# 1-Schematic_EMWAVER_UNO_V3.net
KiCad netlist of a schematic drawn in EasyEDA
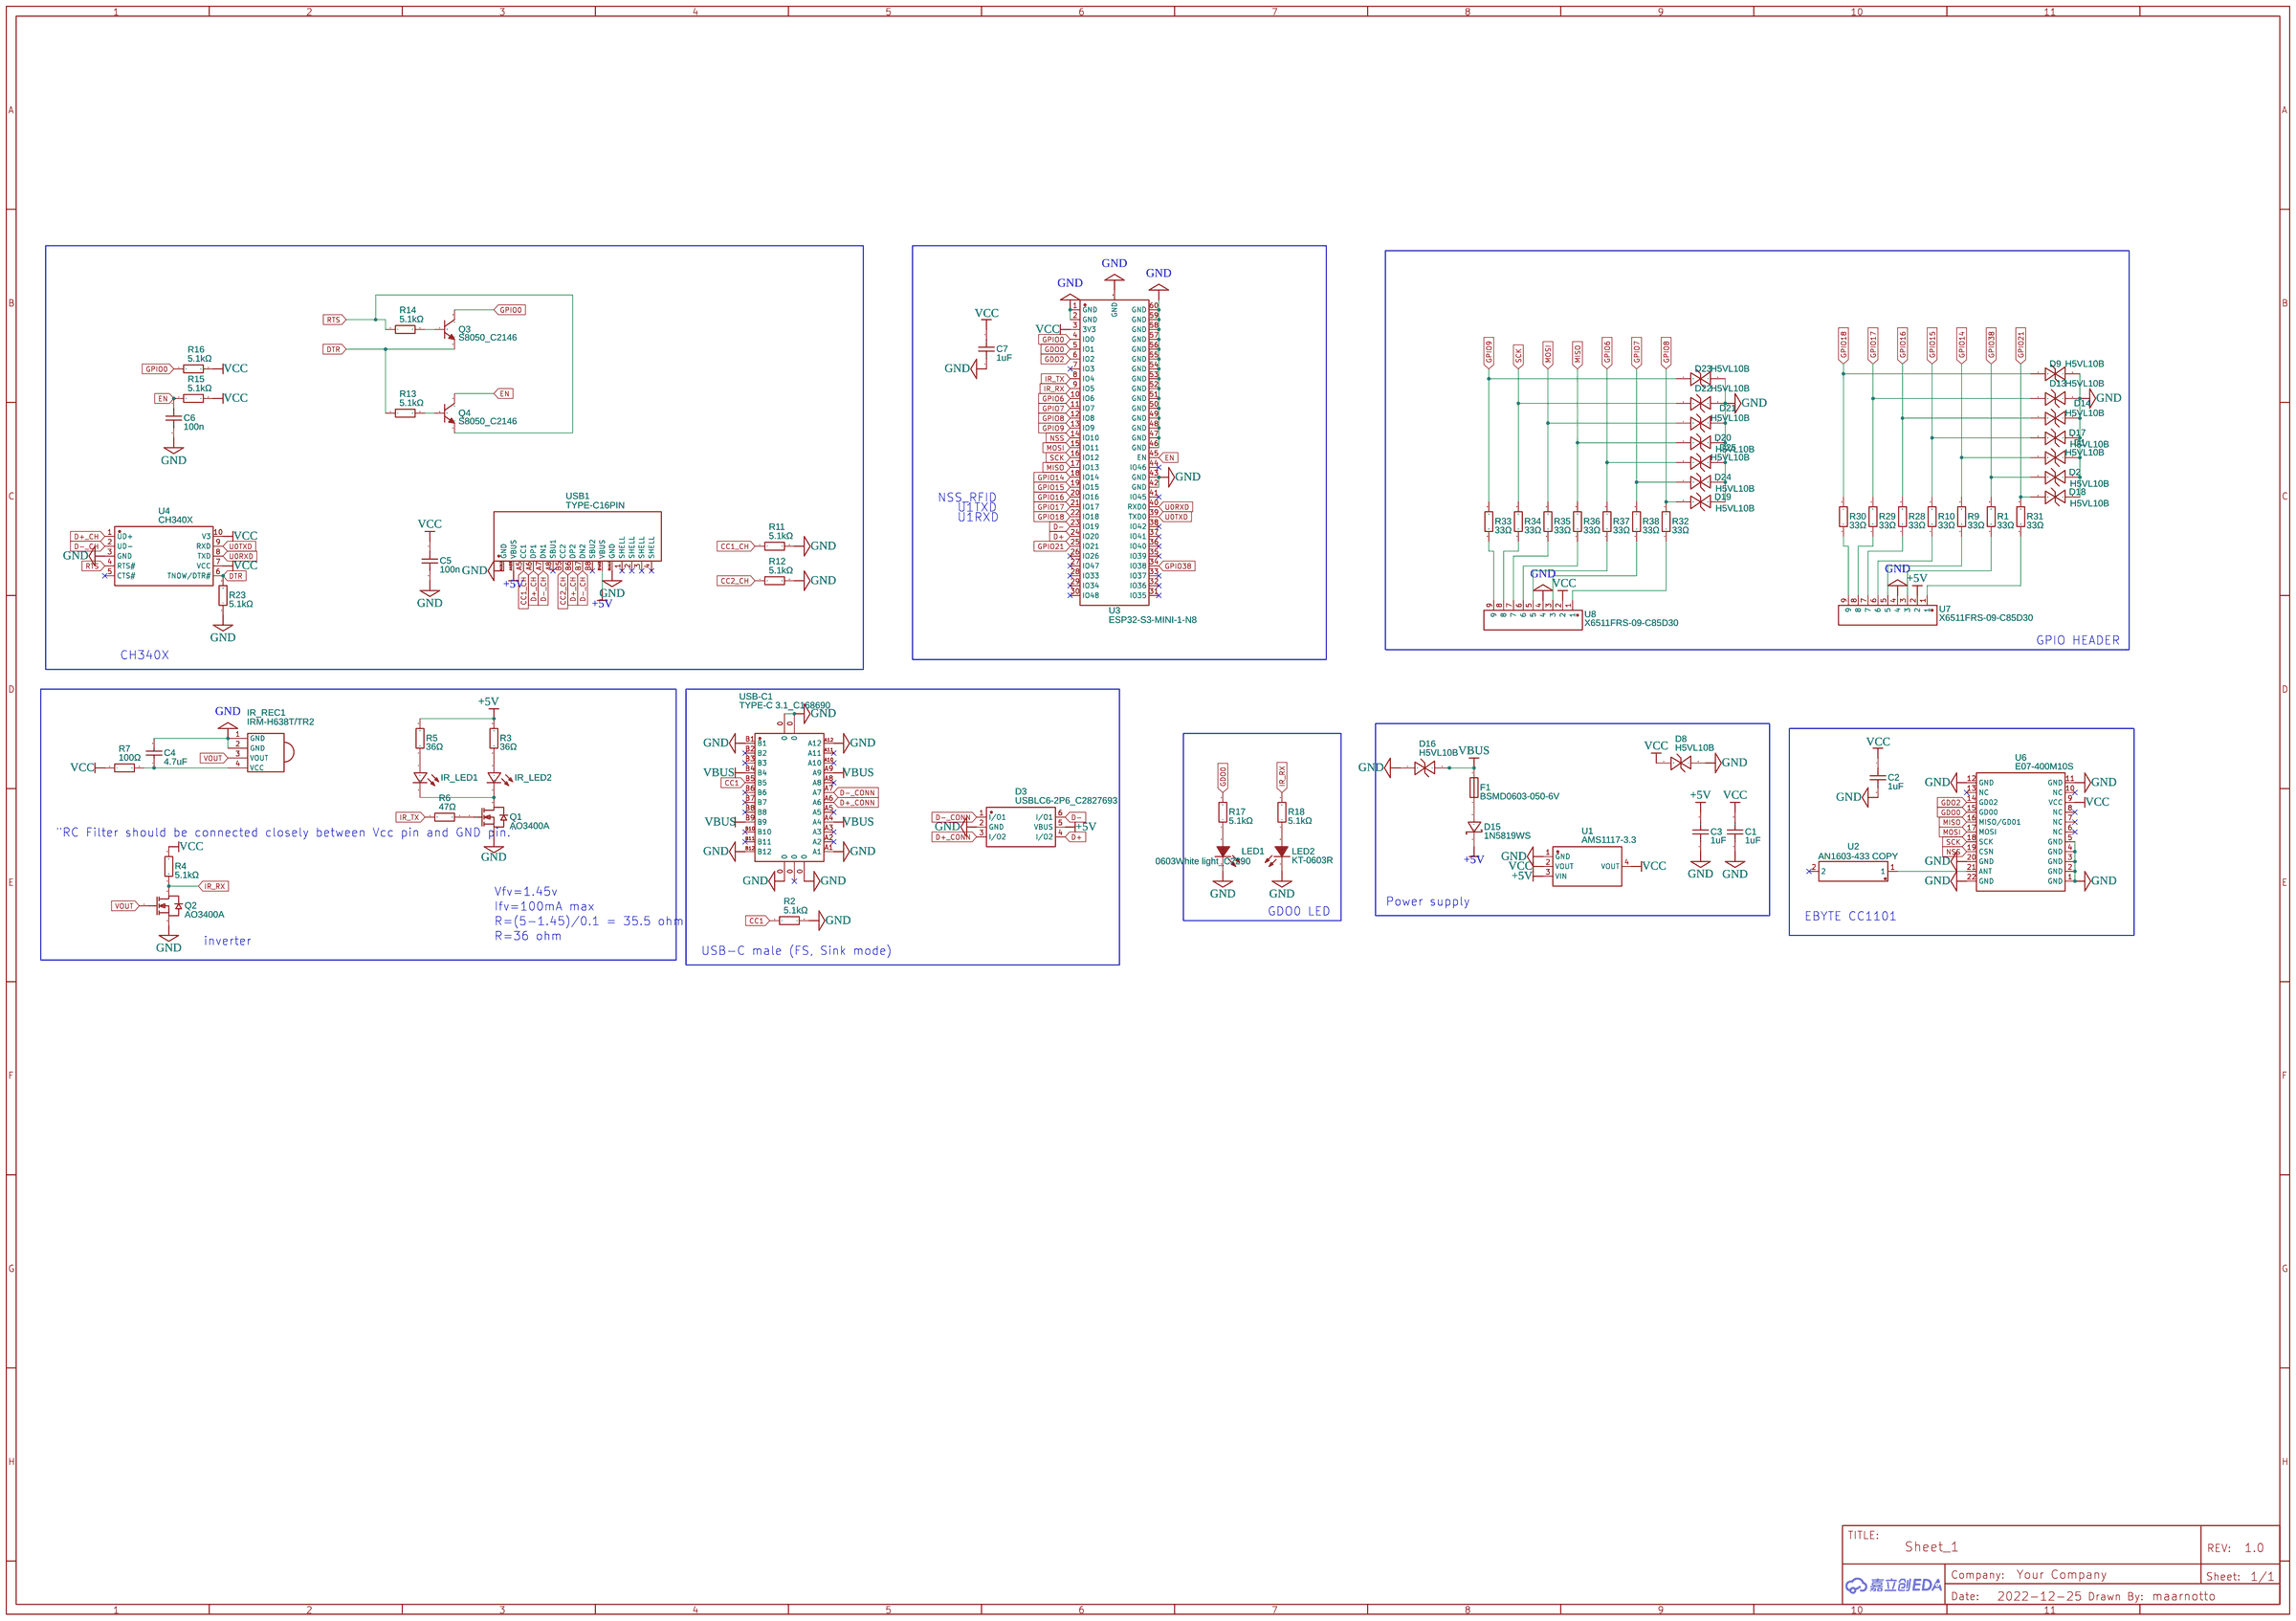
[diagram p0: schematic sheet]

(export (version "E")
  (design (tool "Eeschema 10.0.6"))
  (components
    (comp (ref "C1") (value "1uF") (libsource (lib "") (part "C_0603_US_1")))
    (comp (ref "C2") (value "1uF") (libsource (lib "") (part "C_0603_US")))
    (comp (ref "C3") (value "1uF") (libsource (lib "") (part "C_0603_US_1")))
    (comp (ref "C4")
      (value "4.7uF")
      (fields
        (field (name "Manufacturer Part") "CL10A475KO8NNNC")
        (field (name "Manufacturer") "SAMSUNG(三星)")
      )
      (libsource (lib "") (part "CL10A475KO8NNNC"))
    )
    (comp (ref "C5") (value "100n") (libsource (lib "") (part "C_0603_US")))
    (comp (ref "C6") (value "100n") (libsource (lib "") (part "C_0603_US")))
    (comp (ref "C7") (value "1uF") (libsource (lib "") (part "C_0603_US")))
    (comp (ref "D1")
      (value "H5VL10B")
      (fields (field (name "Manufacturer") "宏迦橙"))
      (libsource (lib "") (part "H5VL10B"))
    )
    (comp (ref "D2")
      (value "H5VL10B")
      (fields (field (name "Manufacturer") "宏迦橙"))
      (libsource (lib "") (part "H5VL10B"))
    )
    (comp (ref "D3")
      (value "USBLC6-2P6_C2827693")
      (fields (field (name "Manufacturer Part") "USBLC6-2P6") (field (name "Manufacturer") "TECH PUBLIC(台舟)"))
      (libsource (lib "") (part "USBLC6-2P6_C2827693"))
    )
    (comp (ref "D8")
      (value "H5VL10B")
      (fields (field (name "Manufacturer") "宏迦橙"))
      (libsource (lib "") (part "H5VL10B"))
    )
    (comp (ref "D9")
      (value "H5VL10B")
      (fields (field (name "Manufacturer") "宏迦橙"))
      (libsource (lib "") (part "H5VL10B"))
    )
    (comp (ref "D13")
      (value "H5VL10B")
      (fields (field (name "Manufacturer") "宏迦橙"))
      (libsource (lib "") (part "H5VL10B"))
    )
    (comp (ref "D14")
      (value "H5VL10B")
      (fields (field (name "Manufacturer") "宏迦橙"))
      (libsource (lib "") (part "H5VL10B"))
    )
    (comp (ref "D15")
      (value "1N5819WS")
      (fields (field (name "Manufacturer") "Hottech(合科泰)"))
      (libsource (lib "") (part "1N5819WS"))
    )
    (comp (ref "D16")
      (value "H5VL10B")
      (fields (field (name "Manufacturer") "宏迦橙"))
      (libsource (lib "") (part "H5VL10B"))
    )
    (comp (ref "D17")
      (value "H5VL10B")
      (fields (field (name "Manufacturer") "宏迦橙"))
      (libsource (lib "") (part "H5VL10B"))
    )
    (comp (ref "D18")
      (value "H5VL10B")
      (fields (field (name "Manufacturer") "宏迦橙"))
      (libsource (lib "") (part "H5VL10B"))
    )
    (comp (ref "D19")
      (value "H5VL10B")
      (fields (field (name "Manufacturer") "宏迦橙"))
      (libsource (lib "") (part "H5VL10B"))
    )
    (comp (ref "D20")
      (value "H5VL10B")
      (fields (field (name "Manufacturer") "宏迦橙"))
      (libsource (lib "") (part "H5VL10B"))
    )
    (comp (ref "D21")
      (value "H5VL10B")
      (fields (field (name "Manufacturer") "宏迦橙"))
      (libsource (lib "") (part "H5VL10B"))
    )
    (comp (ref "D22")
      (value "H5VL10B")
      (fields (field (name "Manufacturer") "宏迦橙"))
      (libsource (lib "") (part "H5VL10B"))
    )
    (comp (ref "D23")
      (value "H5VL10B")
      (fields (field (name "Manufacturer") "宏迦橙"))
      (libsource (lib "") (part "H5VL10B"))
    )
    (comp (ref "D24")
      (value "H5VL10B")
      (fields (field (name "Manufacturer") "宏迦橙"))
      (libsource (lib "") (part "H5VL10B"))
    )
    (comp (ref "D25")
      (value "H5VL10B")
      (fields (field (name "Manufacturer") "宏迦橙"))
      (libsource (lib "") (part "H5VL10B"))
    )
    (comp (ref "F1")
      (value "BSMD0603-050-6V")
      (fields (field (name "Manufacturer") "BHFUSE(佰宏)"))
      (libsource (lib "") (part "BSMD0603-050-6V"))
    )
    (comp (ref "IR_LED1")
      (value "SE03-LP2835S-14100-940")
      (fields (field (name "Manufacturer") "XSSY(旭晟)"))
      (libsource (lib "") (part "SE03-LP2835S-14100-940"))
    )
    (comp (ref "IR_LED2")
      (value "SE03-LP2835S-14100-940")
      (fields (field (name "Manufacturer") "XSSY(旭晟)"))
      (libsource (lib "") (part "SE03-LP2835S-14100-940"))
    )
    (comp (ref "IR_REC1")
      (value "IRM-H638T/TR2")
      (fields (field (name "Manufacturer") "EVERLIGHT(亿光)"))
      (libsource (lib "") (part "IRM-H638T/TR2"))
    )
    (comp (ref "LED1")
      (value "0603White light_C2290")
      (fields (field (name "Manufacturer Part") "KT-0603W") (field (name "Manufacturer") "KENTO"))
      (libsource (lib "") (part "0603White light_C2290"))
    )
    (comp (ref "LED2")
      (value "KT-0603R")
      (fields (field (name "Manufacturer") "KENTO"))
      (libsource (lib "") (part "KT-0603R"))
    )
    (comp (ref "Q1")
      (value "AO3400A")
      (fields (field (name "Manufacturer") "AOS"))
      (libsource (lib "") (part "AO3400A"))
    )
    (comp (ref "Q2")
      (value "AO3400A")
      (fields (field (name "Manufacturer") "AOS"))
      (libsource (lib "") (part "AO3400A"))
    )
    (comp (ref "Q3")
      (value "S8050_C2146")
      (fields (field (name "Manufacturer Part") "S8050 J3Y") (field (name "Manufacturer") "CJ(江苏长电/长晶)"))
      (libsource (lib "") (part "S8050_C2146"))
    )
    (comp (ref "Q4")
      (value "S8050_C2146")
      (fields (field (name "Manufacturer Part") "S8050 J3Y") (field (name "Manufacturer") "CJ(江苏长电/长晶)"))
      (libsource (lib "") (part "S8050_C2146"))
    )
    (comp (ref "R1")
      (value "33Ω")
      (fields
        (field (name "Manufacturer Part") "0402WGF330JTCE")
        (field (name "Manufacturer") "UNI-ROYAL(厚声)")
      )
      (libsource (lib "") (part "0402WGF330JTCE"))
    )
    (comp (ref "R2")
      (value "5.1kΩ")
      (fields
        (field (name "Manufacturer Part") "0603WAF5101T5E")
        (field (name "Manufacturer") "UNI-ROYAL(厚声)")
      )
      (libsource (lib "") (part "0603WAF5101T5E"))
    )
    (comp (ref "R3")
      (value "36Ω")
      (fields
        (field (name "Manufacturer Part") "1206W4J0360T5E")
        (field (name "Manufacturer") "UNI-ROYAL(厚声)")
      )
      (libsource (lib "") (part "1206W4J0360T5E"))
    )
    (comp (ref "R4")
      (value "5.1kΩ")
      (fields
        (field (name "Manufacturer Part") "0603WAF5101T5E")
        (field (name "Manufacturer") "UNI-ROYAL(厚声)")
      )
      (libsource (lib "") (part "0603WAF5101T5E_1"))
    )
    (comp (ref "R5")
      (value "36Ω")
      (fields
        (field (name "Manufacturer Part") "1206W4J0360T5E")
        (field (name "Manufacturer") "UNI-ROYAL(厚声)")
      )
      (libsource (lib "") (part "1206W4J0360T5E"))
    )
    (comp (ref "R6")
      (value "47Ω")
      (fields
        (field (name "Manufacturer Part") "0805W8F470JT5E")
        (field (name "Manufacturer") "UNI-ROYAL(厚声)")
      )
      (libsource (lib "") (part "0805W8F470JT5E"))
    )
    (comp (ref "R7")
      (value "100Ω")
      (fields
        (field (name "Manufacturer Part") "0805W8F1000T5E")
        (field (name "Manufacturer") "UNI-ROYAL(厚声)")
      )
      (libsource (lib "") (part "0805W8F1000T5E"))
    )
    (comp (ref "R9")
      (value "33Ω")
      (fields
        (field (name "Manufacturer Part") "0402WGF330JTCE")
        (field (name "Manufacturer") "UNI-ROYAL(厚声)")
      )
      (libsource (lib "") (part "0402WGF330JTCE"))
    )
    (comp (ref "R10")
      (value "33Ω")
      (fields
        (field (name "Manufacturer Part") "0402WGF330JTCE")
        (field (name "Manufacturer") "UNI-ROYAL(厚声)")
      )
      (libsource (lib "") (part "0402WGF330JTCE"))
    )
    (comp (ref "R11")
      (value "5.1kΩ")
      (fields
        (field (name "Manufacturer Part") "0603WAF5101T5E")
        (field (name "Manufacturer") "UNI-ROYAL(厚声)")
      )
      (libsource (lib "") (part "0603WAF5101T5E"))
    )
    (comp (ref "R12")
      (value "5.1kΩ")
      (fields
        (field (name "Manufacturer Part") "0603WAF5101T5E")
        (field (name "Manufacturer") "UNI-ROYAL(厚声)")
      )
      (libsource (lib "") (part "0603WAF5101T5E"))
    )
    (comp (ref "R13")
      (value "5.1kΩ")
      (fields
        (field (name "Manufacturer Part") "0603WAF5101T5E")
        (field (name "Manufacturer") "UNI-ROYAL(厚声)")
      )
      (libsource (lib "") (part "0603WAF5101T5E"))
    )
    (comp (ref "R14")
      (value "5.1kΩ")
      (fields
        (field (name "Manufacturer Part") "0603WAF5101T5E")
        (field (name "Manufacturer") "UNI-ROYAL(厚声)")
      )
      (libsource (lib "") (part "0603WAF5101T5E"))
    )
    (comp (ref "R15")
      (value "5.1kΩ")
      (fields
        (field (name "Manufacturer Part") "0603WAF5101T5E")
        (field (name "Manufacturer") "UNI-ROYAL(厚声)")
      )
      (libsource (lib "") (part "0603WAF5101T5E"))
    )
    (comp (ref "R16")
      (value "5.1kΩ")
      (fields
        (field (name "Manufacturer Part") "0603WAF5101T5E")
        (field (name "Manufacturer") "UNI-ROYAL(厚声)")
      )
      (libsource (lib "") (part "0603WAF5101T5E"))
    )
    (comp (ref "R17")
      (value "5.1kΩ")
      (fields
        (field (name "Manufacturer Part") "0603WAF5101T5E")
        (field (name "Manufacturer") "UNI-ROYAL(厚声)")
      )
      (libsource (lib "") (part "0603WAF5101T5E_1"))
    )
    (comp (ref "R18")
      (value "5.1kΩ")
      (fields
        (field (name "Manufacturer Part") "0603WAF5101T5E")
        (field (name "Manufacturer") "UNI-ROYAL(厚声)")
      )
      (libsource (lib "") (part "0603WAF5101T5E_1"))
    )
    (comp (ref "R23")
      (value "5.1kΩ")
      (fields
        (field (name "Manufacturer Part") "0603WAF5101T5E")
        (field (name "Manufacturer") "UNI-ROYAL(厚声)")
      )
      (libsource (lib "") (part "0603WAF5101T5E_1"))
    )
    (comp (ref "R28")
      (value "33Ω")
      (fields
        (field (name "Manufacturer Part") "0402WGF330JTCE")
        (field (name "Manufacturer") "UNI-ROYAL(厚声)")
      )
      (libsource (lib "") (part "0402WGF330JTCE"))
    )
    (comp (ref "R29")
      (value "33Ω")
      (fields
        (field (name "Manufacturer Part") "0402WGF330JTCE")
        (field (name "Manufacturer") "UNI-ROYAL(厚声)")
      )
      (libsource (lib "") (part "0402WGF330JTCE"))
    )
    (comp (ref "R30")
      (value "33Ω")
      (fields
        (field (name "Manufacturer Part") "0402WGF330JTCE")
        (field (name "Manufacturer") "UNI-ROYAL(厚声)")
      )
      (libsource (lib "") (part "0402WGF330JTCE"))
    )
    (comp (ref "R31")
      (value "33Ω")
      (fields
        (field (name "Manufacturer Part") "0402WGF330JTCE")
        (field (name "Manufacturer") "UNI-ROYAL(厚声)")
      )
      (libsource (lib "") (part "0402WGF330JTCE"))
    )
    (comp (ref "R32")
      (value "33Ω")
      (fields
        (field (name "Manufacturer Part") "0402WGF330JTCE")
        (field (name "Manufacturer") "UNI-ROYAL(厚声)")
      )
      (libsource (lib "") (part "0402WGF330JTCE"))
    )
    (comp (ref "R33")
      (value "33Ω")
      (fields
        (field (name "Manufacturer Part") "0402WGF330JTCE")
        (field (name "Manufacturer") "UNI-ROYAL(厚声)")
      )
      (libsource (lib "") (part "0402WGF330JTCE"))
    )
    (comp (ref "R34")
      (value "33Ω")
      (fields
        (field (name "Manufacturer Part") "0402WGF330JTCE")
        (field (name "Manufacturer") "UNI-ROYAL(厚声)")
      )
      (libsource (lib "") (part "0402WGF330JTCE"))
    )
    (comp (ref "R35")
      (value "33Ω")
      (fields
        (field (name "Manufacturer Part") "0402WGF330JTCE")
        (field (name "Manufacturer") "UNI-ROYAL(厚声)")
      )
      (libsource (lib "") (part "0402WGF330JTCE"))
    )
    (comp (ref "R36")
      (value "33Ω")
      (fields
        (field (name "Manufacturer Part") "0402WGF330JTCE")
        (field (name "Manufacturer") "UNI-ROYAL(厚声)")
      )
      (libsource (lib "") (part "0402WGF330JTCE"))
    )
    (comp (ref "R37")
      (value "33Ω")
      (fields
        (field (name "Manufacturer Part") "0402WGF330JTCE")
        (field (name "Manufacturer") "UNI-ROYAL(厚声)")
      )
      (libsource (lib "") (part "0402WGF330JTCE"))
    )
    (comp (ref "R38")
      (value "33Ω")
      (fields
        (field (name "Manufacturer Part") "0402WGF330JTCE")
        (field (name "Manufacturer") "UNI-ROYAL(厚声)")
      )
      (libsource (lib "") (part "0402WGF330JTCE"))
    )
    (comp (ref "U1")
      (value "AMS1117-3.3")
      (fields (field (name "Manufacturer") "AMS"))
      (libsource (lib "") (part "AMS1117-3.3"))
    )
    (comp (ref "U2")
      (value "AN1603-433 COPY")
      (fields
        (field (name "Manufacturer Part") "AN1603-433")
        (field (name "Manufacturer") "Rainsun microwave Tech")
      )
      (libsource (lib "") (part "AN1603-433 COPY"))
    )
    (comp (ref "U3")
      (value "ESP32-S3-MINI-1-N8")
      (fields (field (name "Manufacturer") "ESPRESSIF(乐鑫)"))
      (libsource (lib "") (part "ESP32-S3-MINI-1-N8"))
    )
    (comp (ref "U4")
      (value "CH340X")
      (fields (field (name "Manufacturer") "WCH(南京沁恒)"))
      (libsource (lib "") (part "CH340X"))
    )
    (comp (ref "U6")
      (value "E07-400M10S")
      (fields (field (name "Manufacturer") "EBYTE(亿佰特)"))
      (libsource (lib "") (part "E07-400M10S"))
    )
    (comp (ref "U7")
      (value "X6511FRS-09-C85D30")
      (fields (field (name "Manufacturer") "XKB Connectivity(中国星坤)"))
      (libsource (lib "") (part "X6511FRS-09-C85D30"))
    )
    (comp (ref "U8")
      (value "X6511FRS-09-C85D30")
      (fields (field (name "Manufacturer") "XKB Connectivity(中国星坤)"))
      (libsource (lib "") (part "X6511FRS-09-C85D30"))
    )
    (comp (ref "USB-C1")
      (value "TYPE-C 3.1_C168690")
      (fields (field (name "Manufacturer Part") "918-118A2021Y40000") (field (name "Manufacturer") "精拓金"))
      (libsource (lib "") (part "TYPE-C 3.1_C168690"))
    )
    (comp (ref "USB1")
      (value "TYPE-C16PIN")
      (fields (field (name "Manufacturer") "SHOU HAN(首韩)"))
      (libsource (lib "") (part "TYPE-C16PIN"))
    )
  )
  (nets
    (net (code "1") (name "+5V") (class "Default")
      (node (ref "C3") (pin "2") (pinfunction "2_2") (pintype "unspecified"))
      (node (ref "D15") (pin "1") (pinfunction "K_1") (pintype "unspecified"))
      (node (ref "D3") (pin "5") (pinfunction "VBUS_5") (pintype "unspecified"))
      (node (ref "R3") (pin "2") (pinfunction "2_2") (pintype "input"))
      (node (ref "R5") (pin "2") (pinfunction "2_2") (pintype "input"))
      (node (ref "U1") (pin "3") (pinfunction "VIN_3") (pintype "unspecified"))
      (node (ref "U7") (pin "2") (pinfunction "2_2") (pintype "unspecified"))
      (node (ref "USB1") (pin "A4B9") (pinfunction "VBUS_A4B9") (pintype "unspecified"))
      (node (ref "USB1") (pin "B4A9") (pinfunction "VBUS_B4A9") (pintype "unspecified"))
    )
    (net (code "2") (name "CC1") (class "Default")
      (node (ref "R2") (pin "1") (pinfunction "1_1") (pintype "input"))
      (node (ref "USB-C1") (pin "B5") (pinfunction "B5_B5") (pintype "unspecified"))
    )
    (net (code "3") (name "CC1_CH") (class "Default")
      (node (ref "R11") (pin "1") (pinfunction "1_1") (pintype "input"))
      (node (ref "USB1") (pin "A5") (pinfunction "CC1_A5") (pintype "unspecified"))
    )
    (net (code "4") (name "CC2_CH") (class "Default")
      (node (ref "R12") (pin "1") (pinfunction "1_1") (pintype "input"))
      (node (ref "USB1") (pin "B5") (pinfunction "CC2_B5") (pintype "unspecified"))
    )
    (net (code "5") (name "D+") (class "Default")
      (node (ref "D3") (pin "4") (pinfunction "I/O2_4") (pintype "unspecified"))
      (node (ref "U3") (pin "24") (pinfunction "IO20_24") (pintype "unspecified"))
    )
    (net (code "6") (name "D+_CH") (class "Default")
      (node (ref "U4") (pin "1") (pinfunction "UD+_1") (pintype "unspecified"))
      (node (ref "USB1") (pin "A6") (pinfunction "DP1_A6") (pintype "unspecified"))
      (node (ref "USB1") (pin "B6") (pinfunction "DP2_B6") (pintype "unspecified"))
    )
    (net (code "7") (name "D+_CONN") (class "Default")
      (node (ref "D3") (pin "3") (pinfunction "I/O2_3") (pintype "unspecified"))
      (node (ref "USB-C1") (pin "A6") (pinfunction "A6_A6") (pintype "unspecified"))
    )
    (net (code "8") (name "D-") (class "Default")
      (node (ref "D3") (pin "6") (pinfunction "I/O1_6") (pintype "unspecified"))
      (node (ref "U3") (pin "23") (pinfunction "IO19_23") (pintype "unspecified"))
    )
    (net (code "9") (name "D-_CH") (class "Default")
      (node (ref "U4") (pin "2") (pinfunction "UD-_2") (pintype "unspecified"))
      (node (ref "USB1") (pin "A7") (pinfunction "DN1_A7") (pintype "unspecified"))
      (node (ref "USB1") (pin "B7") (pinfunction "DN2_B7") (pintype "unspecified"))
    )
    (net (code "10") (name "D-_CONN") (class "Default")
      (node (ref "D3") (pin "1") (pinfunction "I/O1_1") (pintype "unspecified"))
      (node (ref "USB-C1") (pin "A7") (pinfunction "A7_A7") (pintype "unspecified"))
    )
    (net (code "11") (name "DTR") (class "Default")
      (node (ref "Q3") (pin "2") (pinfunction "E_2") (pintype "unspecified"))
      (node (ref "R13") (pin "1") (pinfunction "1_1") (pintype "input"))
      (node (ref "R23") (pin "2") (pinfunction "2_2") (pintype "input"))
      (node (ref "U4") (pin "6") (pinfunction "TNOW/DTR#_6") (pintype "unspecified"))
    )
    (net (code "12") (name "EN") (class "Default")
      (node (ref "C6") (pin "1") (pinfunction "1_1") (pintype "unspecified"))
      (node (ref "Q4") (pin "3") (pinfunction "C_3") (pintype "unspecified"))
      (node (ref "R15") (pin "1") (pinfunction "1_1") (pintype "input"))
      (node (ref "U3") (pin "45") (pinfunction "EN_45") (pintype "unspecified"))
    )
    (net (code "13") (name "GDO0") (class "Default")
      (node (ref "R17") (pin "2") (pinfunction "2_2") (pintype "input"))
      (node (ref "U3") (pin "5") (pinfunction "IO1_5") (pintype "unspecified"))
      (node (ref "U6") (pin "15") (pinfunction "GD00_15") (pintype "unspecified"))
    )
    (net (code "14") (name "GDO2") (class "Default")
      (node (ref "U3") (pin "6") (pinfunction "IO2_6") (pintype "unspecified"))
      (node (ref "U6") (pin "14") (pinfunction "GD02_14") (pintype "unspecified"))
    )
    (net (code "15") (name "GND") (class "Default")
      (node (ref "C1") (pin "1") (pinfunction "1_1") (pintype "unspecified"))
      (node (ref "C2") (pin "2") (pinfunction "2_2") (pintype "unspecified"))
      (node (ref "C3") (pin "1") (pinfunction "1_1") (pintype "unspecified"))
      (node (ref "C4") (pin "2") (pinfunction "2_2") (pintype "input"))
      (node (ref "C5") (pin "2") (pinfunction "2_2") (pintype "unspecified"))
      (node (ref "C6") (pin "2") (pinfunction "2_2") (pintype "unspecified"))
      (node (ref "C7") (pin "2") (pinfunction "2_2") (pintype "unspecified"))
      (node (ref "D1") (pin "2") (pinfunction "A_2") (pintype "unspecified"))
      (node (ref "D13") (pin "2") (pinfunction "A_2") (pintype "unspecified"))
      (node (ref "D14") (pin "2") (pinfunction "A_2") (pintype "unspecified"))
      (node (ref "D16") (pin "1") (pinfunction "C_1") (pintype "unspecified"))
      (node (ref "D17") (pin "2") (pinfunction "A_2") (pintype "unspecified"))
      (node (ref "D18") (pin "2") (pinfunction "A_2") (pintype "unspecified"))
      (node (ref "D19") (pin "2") (pinfunction "A_2") (pintype "unspecified"))
      (node (ref "D2") (pin "2") (pinfunction "A_2") (pintype "unspecified"))
      (node (ref "D20") (pin "2") (pinfunction "A_2") (pintype "unspecified"))
      (node (ref "D21") (pin "2") (pinfunction "A_2") (pintype "unspecified"))
      (node (ref "D22") (pin "2") (pinfunction "A_2") (pintype "unspecified"))
      (node (ref "D23") (pin "2") (pinfunction "A_2") (pintype "unspecified"))
      (node (ref "D24") (pin "2") (pinfunction "A_2") (pintype "unspecified"))
      (node (ref "D25") (pin "2") (pinfunction "A_2") (pintype "unspecified"))
      (node (ref "D3") (pin "2") (pinfunction "GND_2") (pintype "unspecified"))
      (node (ref "D8") (pin "2") (pinfunction "A_2") (pintype "unspecified"))
      (node (ref "D9") (pin "2") (pinfunction "A_2") (pintype "unspecified"))
      (node (ref "IR_REC1") (pin "1") (pinfunction "GND_1") (pintype "input"))
      (node (ref "IR_REC1") (pin "2") (pinfunction "GND_2") (pintype "input"))
      (node (ref "LED1") (pin "2") (pinfunction "K_2") (pintype "unspecified"))
      (node (ref "LED2") (pin "1") (pinfunction "K_1") (pintype "unspecified"))
      (node (ref "Q1") (pin "2") (pinfunction "S_2") (pintype "unspecified"))
      (node (ref "Q2") (pin "2") (pinfunction "S_2") (pintype "unspecified"))
      (node (ref "R11") (pin "2") (pinfunction "2_2") (pintype "input"))
      (node (ref "R12") (pin "2") (pinfunction "2_2") (pintype "input"))
      (node (ref "R2") (pin "2") (pinfunction "2_2") (pintype "input"))
      (node (ref "R23") (pin "1") (pinfunction "1_1") (pintype "input"))
      (node (ref "U1") (pin "1") (pinfunction "GND_1") (pintype "unspecified"))
      (node (ref "U3") (pin "1") (pinfunction "GND_1") (pintype "unspecified"))
      (node (ref "U3") (pin "2") (pinfunction "GND_2") (pintype "unspecified"))
      (node (ref "U3") (pin "42") (pinfunction "GND_42") (pintype "unspecified"))
      (node (ref "U3") (pin "43") (pinfunction "GND_43") (pintype "unspecified"))
      (node (ref "U3") (pin "46") (pinfunction "GND_46") (pintype "unspecified"))
      (node (ref "U3") (pin "47") (pinfunction "GND_47") (pintype "unspecified"))
      (node (ref "U3") (pin "48") (pinfunction "GND_48") (pintype "unspecified"))
      (node (ref "U3") (pin "49") (pinfunction "GND_49") (pintype "unspecified"))
      (node (ref "U3") (pin "50") (pinfunction "GND_50") (pintype "unspecified"))
      (node (ref "U3") (pin "51") (pinfunction "GND_51") (pintype "unspecified"))
      (node (ref "U3") (pin "52") (pinfunction "GND_52") (pintype "unspecified"))
      (node (ref "U3") (pin "53") (pinfunction "GND_53") (pintype "unspecified"))
      (node (ref "U3") (pin "54") (pinfunction "GND_54") (pintype "unspecified"))
      (node (ref "U3") (pin "55") (pinfunction "GND_55") (pintype "unspecified"))
      (node (ref "U3") (pin "56") (pinfunction "GND_56") (pintype "unspecified"))
      (node (ref "U3") (pin "57") (pinfunction "GND_57") (pintype "unspecified"))
      (node (ref "U3") (pin "58") (pinfunction "GND_58") (pintype "unspecified"))
      (node (ref "U3") (pin "59") (pinfunction "GND_59") (pintype "unspecified"))
      (node (ref "U3") (pin "60") (pinfunction "GND_60") (pintype "unspecified"))
      (node (ref "U3") (pin "GND") (pinfunction "GND_GND") (pintype "unspecified"))
      (node (ref "U4") (pin "3") (pinfunction "GND_3") (pintype "unspecified"))
      (node (ref "U6") (pin "1") (pinfunction "GND_1") (pintype "unspecified"))
      (node (ref "U6") (pin "11") (pinfunction "GND_11") (pintype "unspecified"))
      (node (ref "U6") (pin "12") (pinfunction "GND_12") (pintype "unspecified"))
      (node (ref "U6") (pin "2") (pinfunction "GND_2") (pintype "unspecified"))
      (node (ref "U6") (pin "20") (pinfunction "GND_20") (pintype "unspecified"))
      (node (ref "U6") (pin "22") (pinfunction "GND_22") (pintype "unspecified"))
      (node (ref "U6") (pin "3") (pinfunction "GND_3") (pintype "unspecified"))
      (node (ref "U6") (pin "4") (pinfunction "GND_4") (pintype "unspecified"))
      (node (ref "U6") (pin "5") (pinfunction "GND_5") (pintype "unspecified"))
      (node (ref "U7") (pin "4") (pinfunction "4_4") (pintype "unspecified"))
      (node (ref "U8") (pin "4") (pinfunction "4_4") (pintype "unspecified"))
      (node (ref "USB-C1") (pin "0") (pinfunction "0_0") (pintype "unspecified"))
      (node (ref "USB-C1") (pin "A1") (pinfunction "A1_A1") (pintype "unspecified"))
      (node (ref "USB-C1") (pin "A12") (pinfunction "A12_A12") (pintype "unspecified"))
      (node (ref "USB-C1") (pin "B1") (pinfunction "B1_B1") (pintype "unspecified"))
      (node (ref "USB-C1") (pin "B12") (pinfunction "B12_B12") (pintype "unspecified"))
      (node (ref "USB1") (pin "A1B12") (pinfunction "GND_A1B12") (pintype "unspecified"))
      (node (ref "USB1") (pin "B1A12") (pinfunction "GND_B1A12") (pintype "unspecified"))
    )
    (net (code "16") (name "GPIO0") (class "Default")
      (node (ref "Q3") (pin "3") (pinfunction "C_3") (pintype "unspecified"))
      (node (ref "R16") (pin "1") (pinfunction "1_1") (pintype "input"))
      (node (ref "U3") (pin "4") (pinfunction "IO0_4") (pintype "unspecified"))
    )
    (net (code "17") (name "GPIO6") (class "Default")
      (node (ref "D25") (pin "1") (pinfunction "C_1") (pintype "unspecified"))
      (node (ref "R37") (pin "2") (pinfunction "2_2") (pintype "input"))
      (node (ref "U3") (pin "10") (pinfunction "IO6_10") (pintype "unspecified"))
    )
    (net (code "18") (name "GPIO7") (class "Default")
      (node (ref "D24") (pin "1") (pinfunction "C_1") (pintype "unspecified"))
      (node (ref "R38") (pin "2") (pinfunction "2_2") (pintype "input"))
      (node (ref "U3") (pin "11") (pinfunction "IO7_11") (pintype "unspecified"))
    )
    (net (code "19") (name "GPIO8") (class "Default")
      (node (ref "D19") (pin "1") (pinfunction "C_1") (pintype "unspecified"))
      (node (ref "R32") (pin "2") (pinfunction "2_2") (pintype "input"))
      (node (ref "U3") (pin "12") (pinfunction "IO8_12") (pintype "unspecified"))
    )
    (net (code "20") (name "GPIO9") (class "Default")
      (node (ref "D23") (pin "1") (pinfunction "C_1") (pintype "unspecified"))
      (node (ref "R33") (pin "2") (pinfunction "2_2") (pintype "input"))
      (node (ref "U3") (pin "13") (pinfunction "IO9_13") (pintype "unspecified"))
    )
    (net (code "21") (name "GPIO14") (class "Default")
      (node (ref "D1") (pin "1") (pinfunction "C_1") (pintype "unspecified"))
      (node (ref "R9") (pin "2") (pinfunction "2_2") (pintype "input"))
      (node (ref "U3") (pin "18") (pinfunction "IO14_18") (pintype "unspecified"))
    )
    (net (code "22") (name "GPIO15") (class "Default")
      (node (ref "D17") (pin "1") (pinfunction "C_1") (pintype "unspecified"))
      (node (ref "R10") (pin "2") (pinfunction "2_2") (pintype "input"))
      (node (ref "U3") (pin "19") (pinfunction "IO15_19") (pintype "unspecified"))
    )
    (net (code "23") (name "GPIO16") (class "Default")
      (node (ref "D14") (pin "1") (pinfunction "C_1") (pintype "unspecified"))
      (node (ref "R28") (pin "2") (pinfunction "2_2") (pintype "input"))
      (node (ref "U3") (pin "20") (pinfunction "IO16_20") (pintype "unspecified"))
    )
    (net (code "24") (name "GPIO17") (class "Default")
      (node (ref "D13") (pin "1") (pinfunction "C_1") (pintype "unspecified"))
      (node (ref "R29") (pin "2") (pinfunction "2_2") (pintype "input"))
      (node (ref "U3") (pin "21") (pinfunction "IO17_21") (pintype "unspecified"))
    )
    (net (code "25") (name "GPIO18") (class "Default")
      (node (ref "D9") (pin "1") (pinfunction "C_1") (pintype "unspecified"))
      (node (ref "R30") (pin "2") (pinfunction "2_2") (pintype "input"))
      (node (ref "U3") (pin "22") (pinfunction "IO18_22") (pintype "unspecified"))
    )
    (net (code "26") (name "GPIO21") (class "Default")
      (node (ref "D18") (pin "1") (pinfunction "C_1") (pintype "unspecified"))
      (node (ref "R31") (pin "2") (pinfunction "2_2") (pintype "input"))
      (node (ref "U3") (pin "25") (pinfunction "IO21_25") (pintype "unspecified"))
    )
    (net (code "27") (name "GPIO38") (class "Default")
      (node (ref "D2") (pin "1") (pinfunction "C_1") (pintype "unspecified"))
      (node (ref "R1") (pin "2") (pinfunction "2_2") (pintype "input"))
      (node (ref "U3") (pin "34") (pinfunction "IO38_34") (pintype "unspecified"))
    )
    (net (code "28") (name "IR_RX") (class "Default")
      (node (ref "Q2") (pin "3") (pinfunction "D_3") (pintype "unspecified"))
      (node (ref "R18") (pin "2") (pinfunction "2_2") (pintype "input"))
      (node (ref "R4") (pin "1") (pinfunction "1_1") (pintype "input"))
      (node (ref "U3") (pin "9") (pinfunction "IO5_9") (pintype "unspecified"))
    )
    (net (code "29") (name "IR_TX") (class "Default")
      (node (ref "R6") (pin "1") (pinfunction "1_1") (pintype "input"))
      (node (ref "U3") (pin "8") (pinfunction "IO4_8") (pintype "unspecified"))
    )
    (net (code "30") (name "MISO") (class "Default")
      (node (ref "D20") (pin "1") (pinfunction "C_1") (pintype "unspecified"))
      (node (ref "R36") (pin "2") (pinfunction "2_2") (pintype "input"))
      (node (ref "U3") (pin "17") (pinfunction "IO13_17") (pintype "unspecified"))
      (node (ref "U6") (pin "16") (pinfunction "MISO/GD01_16") (pintype "unspecified"))
    )
    (net (code "31") (name "MOSI") (class "Default")
      (node (ref "D21") (pin "1") (pinfunction "C_1") (pintype "unspecified"))
      (node (ref "R35") (pin "2") (pinfunction "2_2") (pintype "input"))
      (node (ref "U3") (pin "15") (pinfunction "IO11_15") (pintype "unspecified"))
      (node (ref "U6") (pin "17") (pinfunction "MOSI_17") (pintype "unspecified"))
    )
    (net (code "32") (name "NSS") (class "Default")
      (node (ref "U3") (pin "14") (pinfunction "IO10_14") (pintype "unspecified"))
      (node (ref "U6") (pin "19") (pinfunction "CSN_19") (pintype "unspecified"))
    )
    (net (code "33") (name "Net-(D15-A)") (class "Default")
      (node (ref "D15") (pin "2") (pinfunction "A_2") (pintype "unspecified"))
      (node (ref "F1") (pin "1") (pinfunction "1_1") (pintype "unspecified"))
    )
    (net (code "34") (name "Net-(IR_LED1-A)") (class "Default")
      (node (ref "IR_LED1") (pin "1") (pinfunction "A_1") (pintype "unspecified"))
      (node (ref "R5") (pin "1") (pinfunction "1_1") (pintype "input"))
    )
    (net (code "35") (name "Net-(IR_LED1-C)") (class "Default")
      (node (ref "IR_LED1") (pin "2") (pinfunction "C_2") (pintype "unspecified"))
      (node (ref "IR_LED2") (pin "2") (pinfunction "C_2") (pintype "unspecified"))
      (node (ref "Q1") (pin "3") (pinfunction "D_3") (pintype "unspecified"))
    )
    (net (code "36") (name "Net-(IR_LED2-A)") (class "Default")
      (node (ref "IR_LED2") (pin "1") (pinfunction "A_1") (pintype "unspecified"))
      (node (ref "R3") (pin "1") (pinfunction "1_1") (pintype "input"))
    )
    (net (code "37") (name "Net-(IR_REC1-VCC)") (class "Default")
      (node (ref "C4") (pin "1") (pinfunction "1_1") (pintype "input"))
      (node (ref "IR_REC1") (pin "4") (pinfunction "VCC_4") (pintype "input"))
      (node (ref "R7") (pin "2") (pinfunction "2_2") (pintype "input"))
    )
    (net (code "38") (name "Net-(LED1-A)") (class "Default")
      (node (ref "LED1") (pin "1") (pinfunction "A_1") (pintype "unspecified"))
      (node (ref "R17") (pin "1") (pinfunction "1_1") (pintype "input"))
    )
    (net (code "39") (name "Net-(LED2-A)") (class "Default")
      (node (ref "LED2") (pin "2") (pinfunction "A_2") (pintype "unspecified"))
      (node (ref "R18") (pin "1") (pinfunction "1_1") (pintype "input"))
    )
    (net (code "40") (name "Net-(Q1-G)") (class "Default")
      (node (ref "Q1") (pin "1") (pinfunction "G_1") (pintype "unspecified"))
      (node (ref "R6") (pin "2") (pinfunction "2_2") (pintype "input"))
    )
    (net (code "41") (name "Net-(Q3-B)") (class "Default")
      (node (ref "Q3") (pin "1") (pinfunction "B_1") (pintype "unspecified"))
      (node (ref "R14") (pin "2") (pinfunction "2_2") (pintype "input"))
    )
    (net (code "42") (name "Net-(Q4-B)") (class "Default")
      (node (ref "Q4") (pin "1") (pinfunction "B_1") (pintype "unspecified"))
      (node (ref "R13") (pin "2") (pinfunction "2_2") (pintype "input"))
    )
    (net (code "43") (name "Net-(R1-Pad1)") (class "Default")
      (node (ref "R1") (pin "1") (pinfunction "1_1") (pintype "input"))
      (node (ref "U7") (pin "3") (pinfunction "3_3") (pintype "unspecified"))
    )
    (net (code "44") (name "Net-(R9-Pad1)") (class "Default")
      (node (ref "R9") (pin "1") (pinfunction "1_1") (pintype "input"))
      (node (ref "U7") (pin "5") (pinfunction "5_5") (pintype "unspecified"))
    )
    (net (code "45") (name "Net-(R10-Pad1)") (class "Default")
      (node (ref "R10") (pin "1") (pinfunction "1_1") (pintype "input"))
      (node (ref "U7") (pin "6") (pinfunction "6_6") (pintype "unspecified"))
    )
    (net (code "46") (name "Net-(R28-Pad1)") (class "Default")
      (node (ref "R28") (pin "1") (pinfunction "1_1") (pintype "input"))
      (node (ref "U7") (pin "7") (pinfunction "7_7") (pintype "unspecified"))
    )
    (net (code "47") (name "Net-(R29-Pad1)") (class "Default")
      (node (ref "R29") (pin "1") (pinfunction "1_1") (pintype "input"))
      (node (ref "U7") (pin "8") (pinfunction "8_8") (pintype "unspecified"))
    )
    (net (code "48") (name "Net-(R30-Pad1)") (class "Default")
      (node (ref "R30") (pin "1") (pinfunction "1_1") (pintype "input"))
      (node (ref "U7") (pin "9") (pinfunction "9_9") (pintype "unspecified"))
    )
    (net (code "49") (name "Net-(R31-Pad1)") (class "Default")
      (node (ref "R31") (pin "1") (pinfunction "1_1") (pintype "input"))
      (node (ref "U7") (pin "1") (pinfunction "1_1") (pintype "unspecified"))
    )
    (net (code "50") (name "Net-(R32-Pad1)") (class "Default")
      (node (ref "R32") (pin "1") (pinfunction "1_1") (pintype "input"))
      (node (ref "U8") (pin "1") (pinfunction "1_1") (pintype "unspecified"))
    )
    (net (code "51") (name "Net-(R33-Pad1)") (class "Default")
      (node (ref "R33") (pin "1") (pinfunction "1_1") (pintype "input"))
      (node (ref "U8") (pin "9") (pinfunction "9_9") (pintype "unspecified"))
    )
    (net (code "52") (name "Net-(R34-Pad1)") (class "Default")
      (node (ref "R34") (pin "1") (pinfunction "1_1") (pintype "input"))
      (node (ref "U8") (pin "8") (pinfunction "8_8") (pintype "unspecified"))
    )
    (net (code "53") (name "Net-(R35-Pad1)") (class "Default")
      (node (ref "R35") (pin "1") (pinfunction "1_1") (pintype "input"))
      (node (ref "U8") (pin "7") (pinfunction "7_7") (pintype "unspecified"))
    )
    (net (code "54") (name "Net-(R36-Pad1)") (class "Default")
      (node (ref "R36") (pin "1") (pinfunction "1_1") (pintype "input"))
      (node (ref "U8") (pin "6") (pinfunction "6_6") (pintype "unspecified"))
    )
    (net (code "55") (name "Net-(R37-Pad1)") (class "Default")
      (node (ref "R37") (pin "1") (pinfunction "1_1") (pintype "input"))
      (node (ref "U8") (pin "5") (pinfunction "5_5") (pintype "unspecified"))
    )
    (net (code "56") (name "Net-(R38-Pad1)") (class "Default")
      (node (ref "R38") (pin "1") (pinfunction "1_1") (pintype "input"))
      (node (ref "U8") (pin "3") (pinfunction "3_3") (pintype "unspecified"))
    )
    (net (code "57") (name "Net-(U6-ANT)") (class "Default")
      (node (ref "U2") (pin "1") (pinfunction "1_1") (pintype "unspecified"))
      (node (ref "U6") (pin "21") (pinfunction "ANT_21") (pintype "unspecified"))
    )
    (net (code "58") (name "RTS") (class "Default")
      (node (ref "Q4") (pin "2") (pinfunction "E_2") (pintype "unspecified"))
      (node (ref "R14") (pin "1") (pinfunction "1_1") (pintype "input"))
      (node (ref "U4") (pin "4") (pinfunction "RTS#_4") (pintype "unspecified"))
    )
    (net (code "59") (name "SCK") (class "Default")
      (node (ref "D22") (pin "1") (pinfunction "C_1") (pintype "unspecified"))
      (node (ref "R34") (pin "2") (pinfunction "2_2") (pintype "input"))
      (node (ref "U3") (pin "16") (pinfunction "IO12_16") (pintype "unspecified"))
      (node (ref "U6") (pin "18") (pinfunction "SCK_18") (pintype "unspecified"))
    )
    (net (code "60") (name "U0RXD") (class "Default")
      (node (ref "U3") (pin "40") (pinfunction "RXD0_40") (pintype "unspecified"))
      (node (ref "U4") (pin "8") (pinfunction "TXD_8") (pintype "unspecified"))
    )
    (net (code "61") (name "U0TXD") (class "Default")
      (node (ref "U3") (pin "39") (pinfunction "TXD0_39") (pintype "unspecified"))
      (node (ref "U4") (pin "9") (pinfunction "RXD_9") (pintype "unspecified"))
    )
    (net (code "62") (name "VBUS") (class "Default")
      (node (ref "D16") (pin "2") (pinfunction "A_2") (pintype "unspecified"))
      (node (ref "F1") (pin "2") (pinfunction "2_2") (pintype "unspecified"))
      (node (ref "USB-C1") (pin "A4") (pinfunction "A4_A4") (pintype "unspecified"))
      (node (ref "USB-C1") (pin "A9") (pinfunction "A9_A9") (pintype "unspecified"))
      (node (ref "USB-C1") (pin "B4") (pinfunction "B4_B4") (pintype "unspecified"))
      (node (ref "USB-C1") (pin "B9") (pinfunction "B9_B9") (pintype "unspecified"))
    )
    (net (code "63") (name "VCC") (class "Default")
      (node (ref "C1") (pin "2") (pinfunction "2_2") (pintype "unspecified"))
      (node (ref "C2") (pin "1") (pinfunction "1_1") (pintype "unspecified"))
      (node (ref "C5") (pin "1") (pinfunction "1_1") (pintype "unspecified"))
      (node (ref "C7") (pin "1") (pinfunction "1_1") (pintype "unspecified"))
      (node (ref "D8") (pin "1") (pinfunction "C_1") (pintype "unspecified"))
      (node (ref "R15") (pin "2") (pinfunction "2_2") (pintype "input"))
      (node (ref "R16") (pin "2") (pinfunction "2_2") (pintype "input"))
      (node (ref "R4") (pin "2") (pinfunction "2_2") (pintype "input"))
      (node (ref "R7") (pin "1") (pinfunction "1_1") (pintype "input"))
      (node (ref "U1") (pin "2") (pinfunction "VOUT_2") (pintype "unspecified"))
      (node (ref "U1") (pin "4") (pinfunction "VOUT_4") (pintype "unspecified"))
      (node (ref "U3") (pin "3") (pinfunction "3V3_3") (pintype "unspecified"))
      (node (ref "U4") (pin "10") (pinfunction "V3_10") (pintype "unspecified"))
      (node (ref "U4") (pin "7") (pinfunction "VCC_7") (pintype "unspecified"))
      (node (ref "U6") (pin "9") (pinfunction "VCC_9") (pintype "unspecified"))
      (node (ref "U8") (pin "2") (pinfunction "2_2") (pintype "unspecified"))
    )
    (net (code "64") (name "VOUT") (class "Default")
      (node (ref "IR_REC1") (pin "3") (pinfunction "VOUT_3") (pintype "input"))
      (node (ref "Q2") (pin "1") (pinfunction "G_1") (pintype "unspecified"))
    )
    (net (code "65") (name "unconnected-(U2-Pad2)") (class "Default")
      (node (ref "U2") (pin "2") (pinfunction "2_2") (pintype "unspecified+no_connect"))
    )
    (net (code "66") (name "unconnected-(U3-IO3-Pad7)") (class "Default")
      (node (ref "U3") (pin "7") (pinfunction "IO3_7") (pintype "unspecified+no_connect"))
    )
    (net (code "67") (name "unconnected-(U3-IO26-Pad26)") (class "Default")
      (node (ref "U3") (pin "26") (pinfunction "IO26_26") (pintype "unspecified+no_connect"))
    )
    (net (code "68") (name "unconnected-(U3-IO33-Pad28)") (class "Default")
      (node (ref "U3") (pin "28") (pinfunction "IO33_28") (pintype "unspecified+no_connect"))
    )
    (net (code "69") (name "unconnected-(U3-IO34-Pad29)") (class "Default")
      (node (ref "U3") (pin "29") (pinfunction "IO34_29") (pintype "unspecified+no_connect"))
    )
    (net (code "70") (name "unconnected-(U3-IO35-Pad31)") (class "Default")
      (node (ref "U3") (pin "31") (pinfunction "IO35_31") (pintype "unspecified+no_connect"))
    )
    (net (code "71") (name "unconnected-(U3-IO36-Pad32)") (class "Default")
      (node (ref "U3") (pin "32") (pinfunction "IO36_32") (pintype "unspecified+no_connect"))
    )
    (net (code "72") (name "unconnected-(U3-IO37-Pad33)") (class "Default")
      (node (ref "U3") (pin "33") (pinfunction "IO37_33") (pintype "unspecified+no_connect"))
    )
    (net (code "73") (name "unconnected-(U3-IO39-Pad35)") (class "Default")
      (node (ref "U3") (pin "35") (pinfunction "IO39_35") (pintype "unspecified+no_connect"))
    )
    (net (code "74") (name "unconnected-(U3-IO40-Pad36)") (class "Default")
      (node (ref "U3") (pin "36") (pinfunction "IO40_36") (pintype "unspecified+no_connect"))
    )
    (net (code "75") (name "unconnected-(U3-IO41-Pad37)") (class "Default")
      (node (ref "U3") (pin "37") (pinfunction "IO41_37") (pintype "unspecified+no_connect"))
    )
    (net (code "76") (name "unconnected-(U3-IO42-Pad38)") (class "Default")
      (node (ref "U3") (pin "38") (pinfunction "IO42_38") (pintype "unspecified+no_connect"))
    )
    (net (code "77") (name "unconnected-(U3-IO45-Pad41)") (class "Default")
      (node (ref "U3") (pin "41") (pinfunction "IO45_41") (pintype "unspecified+no_connect"))
    )
    (net (code "78") (name "unconnected-(U3-IO46-Pad44)") (class "Default")
      (node (ref "U3") (pin "44") (pinfunction "IO46_44") (pintype "unspecified+no_connect"))
    )
    (net (code "79") (name "unconnected-(U3-IO47-Pad27)") (class "Default")
      (node (ref "U3") (pin "27") (pinfunction "IO47_27") (pintype "unspecified+no_connect"))
    )
    (net (code "80") (name "unconnected-(U3-IO48-Pad30)") (class "Default")
      (node (ref "U3") (pin "30") (pinfunction "IO48_30") (pintype "unspecified+no_connect"))
    )
    (net (code "81") (name "unconnected-(U4-CTS#-Pad5)") (class "Default")
      (node (ref "U4") (pin "5") (pinfunction "CTS#_5") (pintype "unspecified+no_connect"))
    )
    (net (code "82") (name "unconnected-(U6-NC-Pad6)") (class "Default")
      (node (ref "U6") (pin "6") (pinfunction "NC_6") (pintype "unspecified+no_connect"))
    )
    (net (code "83") (name "unconnected-(U6-NC-Pad7)") (class "Default")
      (node (ref "U6") (pin "7") (pinfunction "NC_7") (pintype "unspecified+no_connect"))
    )
    (net (code "84") (name "unconnected-(U6-NC-Pad8)") (class "Default")
      (node (ref "U6") (pin "8") (pinfunction "NC_8") (pintype "unspecified+no_connect"))
    )
    (net (code "85") (name "unconnected-(U6-NC-Pad10)") (class "Default")
      (node (ref "U6") (pin "10") (pinfunction "NC_10") (pintype "unspecified+no_connect"))
    )
    (net (code "86") (name "unconnected-(U6-NC-Pad13)") (class "Default")
      (node (ref "U6") (pin "13") (pinfunction "NC_13") (pintype "unspecified+no_connect"))
    )
    (net (code "87") (name "unconnected-(USB-C1-Pad0)") (class "Default")
      (node (ref "USB-C1") (pin "0") (pinfunction "0_0") (pintype "unspecified+no_connect"))
    )
    (net (code "88") (name "unconnected-(USB-C1-PadA2)") (class "Default")
      (node (ref "USB-C1") (pin "A2") (pinfunction "A2_A2") (pintype "unspecified+no_connect"))
    )
    (net (code "89") (name "unconnected-(USB-C1-PadA3)") (class "Default")
      (node (ref "USB-C1") (pin "A3") (pinfunction "A3_A3") (pintype "unspecified+no_connect"))
    )
    (net (code "90") (name "unconnected-(USB-C1-PadA5)") (class "Default")
      (node (ref "USB-C1") (pin "A5") (pinfunction "A5_A5") (pintype "unspecified+no_connect"))
    )
    (net (code "91") (name "unconnected-(USB-C1-PadA8)") (class "Default")
      (node (ref "USB-C1") (pin "A8") (pinfunction "A8_A8") (pintype "unspecified+no_connect"))
    )
    (net (code "92") (name "unconnected-(USB-C1-PadA10)") (class "Default")
      (node (ref "USB-C1") (pin "A10") (pinfunction "A10_A10") (pintype "unspecified+no_connect"))
    )
    (net (code "93") (name "unconnected-(USB-C1-PadA11)") (class "Default")
      (node (ref "USB-C1") (pin "A11") (pinfunction "A11_A11") (pintype "unspecified+no_connect"))
    )
    (net (code "94") (name "unconnected-(USB-C1-PadB2)") (class "Default")
      (node (ref "USB-C1") (pin "B2") (pinfunction "B2_B2") (pintype "unspecified+no_connect"))
    )
    (net (code "95") (name "unconnected-(USB-C1-PadB3)") (class "Default")
      (node (ref "USB-C1") (pin "B3") (pinfunction "B3_B3") (pintype "unspecified+no_connect"))
    )
    (net (code "96") (name "unconnected-(USB-C1-PadB6)") (class "Default")
      (node (ref "USB-C1") (pin "B6") (pinfunction "B6_B6") (pintype "unspecified+no_connect"))
    )
    (net (code "97") (name "unconnected-(USB-C1-PadB7)") (class "Default")
      (node (ref "USB-C1") (pin "B7") (pinfunction "B7_B7") (pintype "unspecified+no_connect"))
    )
    (net (code "98") (name "unconnected-(USB-C1-PadB8)") (class "Default")
      (node (ref "USB-C1") (pin "B8") (pinfunction "B8_B8") (pintype "unspecified+no_connect"))
    )
    (net (code "99") (name "unconnected-(USB-C1-PadB10)") (class "Default")
      (node (ref "USB-C1") (pin "B10") (pinfunction "B10_B10") (pintype "unspecified+no_connect"))
    )
    (net (code "100") (name "unconnected-(USB-C1-PadB11)") (class "Default")
      (node (ref "USB-C1") (pin "B11") (pinfunction "B11_B11") (pintype "unspecified+no_connect"))
    )
    (net (code "101") (name "unconnected-(USB1-SBU1-PadA8)") (class "Default")
      (node (ref "USB1") (pin "A8") (pinfunction "SBU1_A8") (pintype "unspecified+no_connect"))
    )
    (net (code "102") (name "unconnected-(USB1-SBU2-PadB8)") (class "Default")
      (node (ref "USB1") (pin "B8") (pinfunction "SBU2_B8") (pintype "unspecified+no_connect"))
    )
    (net (code "103") (name "unconnected-(USB1-SHELL-Pad1)") (class "Default")
      (node (ref "USB1") (pin "1") (pinfunction "SHELL_1") (pintype "unspecified+no_connect"))
    )
    (net (code "104") (name "unconnected-(USB1-SHELL-Pad2)") (class "Default")
      (node (ref "USB1") (pin "2") (pinfunction "SHELL_2") (pintype "unspecified+no_connect"))
    )
    (net (code "105") (name "unconnected-(USB1-SHELL-Pad3)") (class "Default")
      (node (ref "USB1") (pin "3") (pinfunction "SHELL_3") (pintype "unspecified+no_connect"))
    )
    (net (code "106") (name "unconnected-(USB1-SHELL-Pad4)") (class "Default")
      (node (ref "USB1") (pin "4") (pinfunction "SHELL_4") (pintype "unspecified+no_connect"))
    )
  )
)
